# 09_Misc.net
KiCad netlist of a schematic drawn in Altium Designer
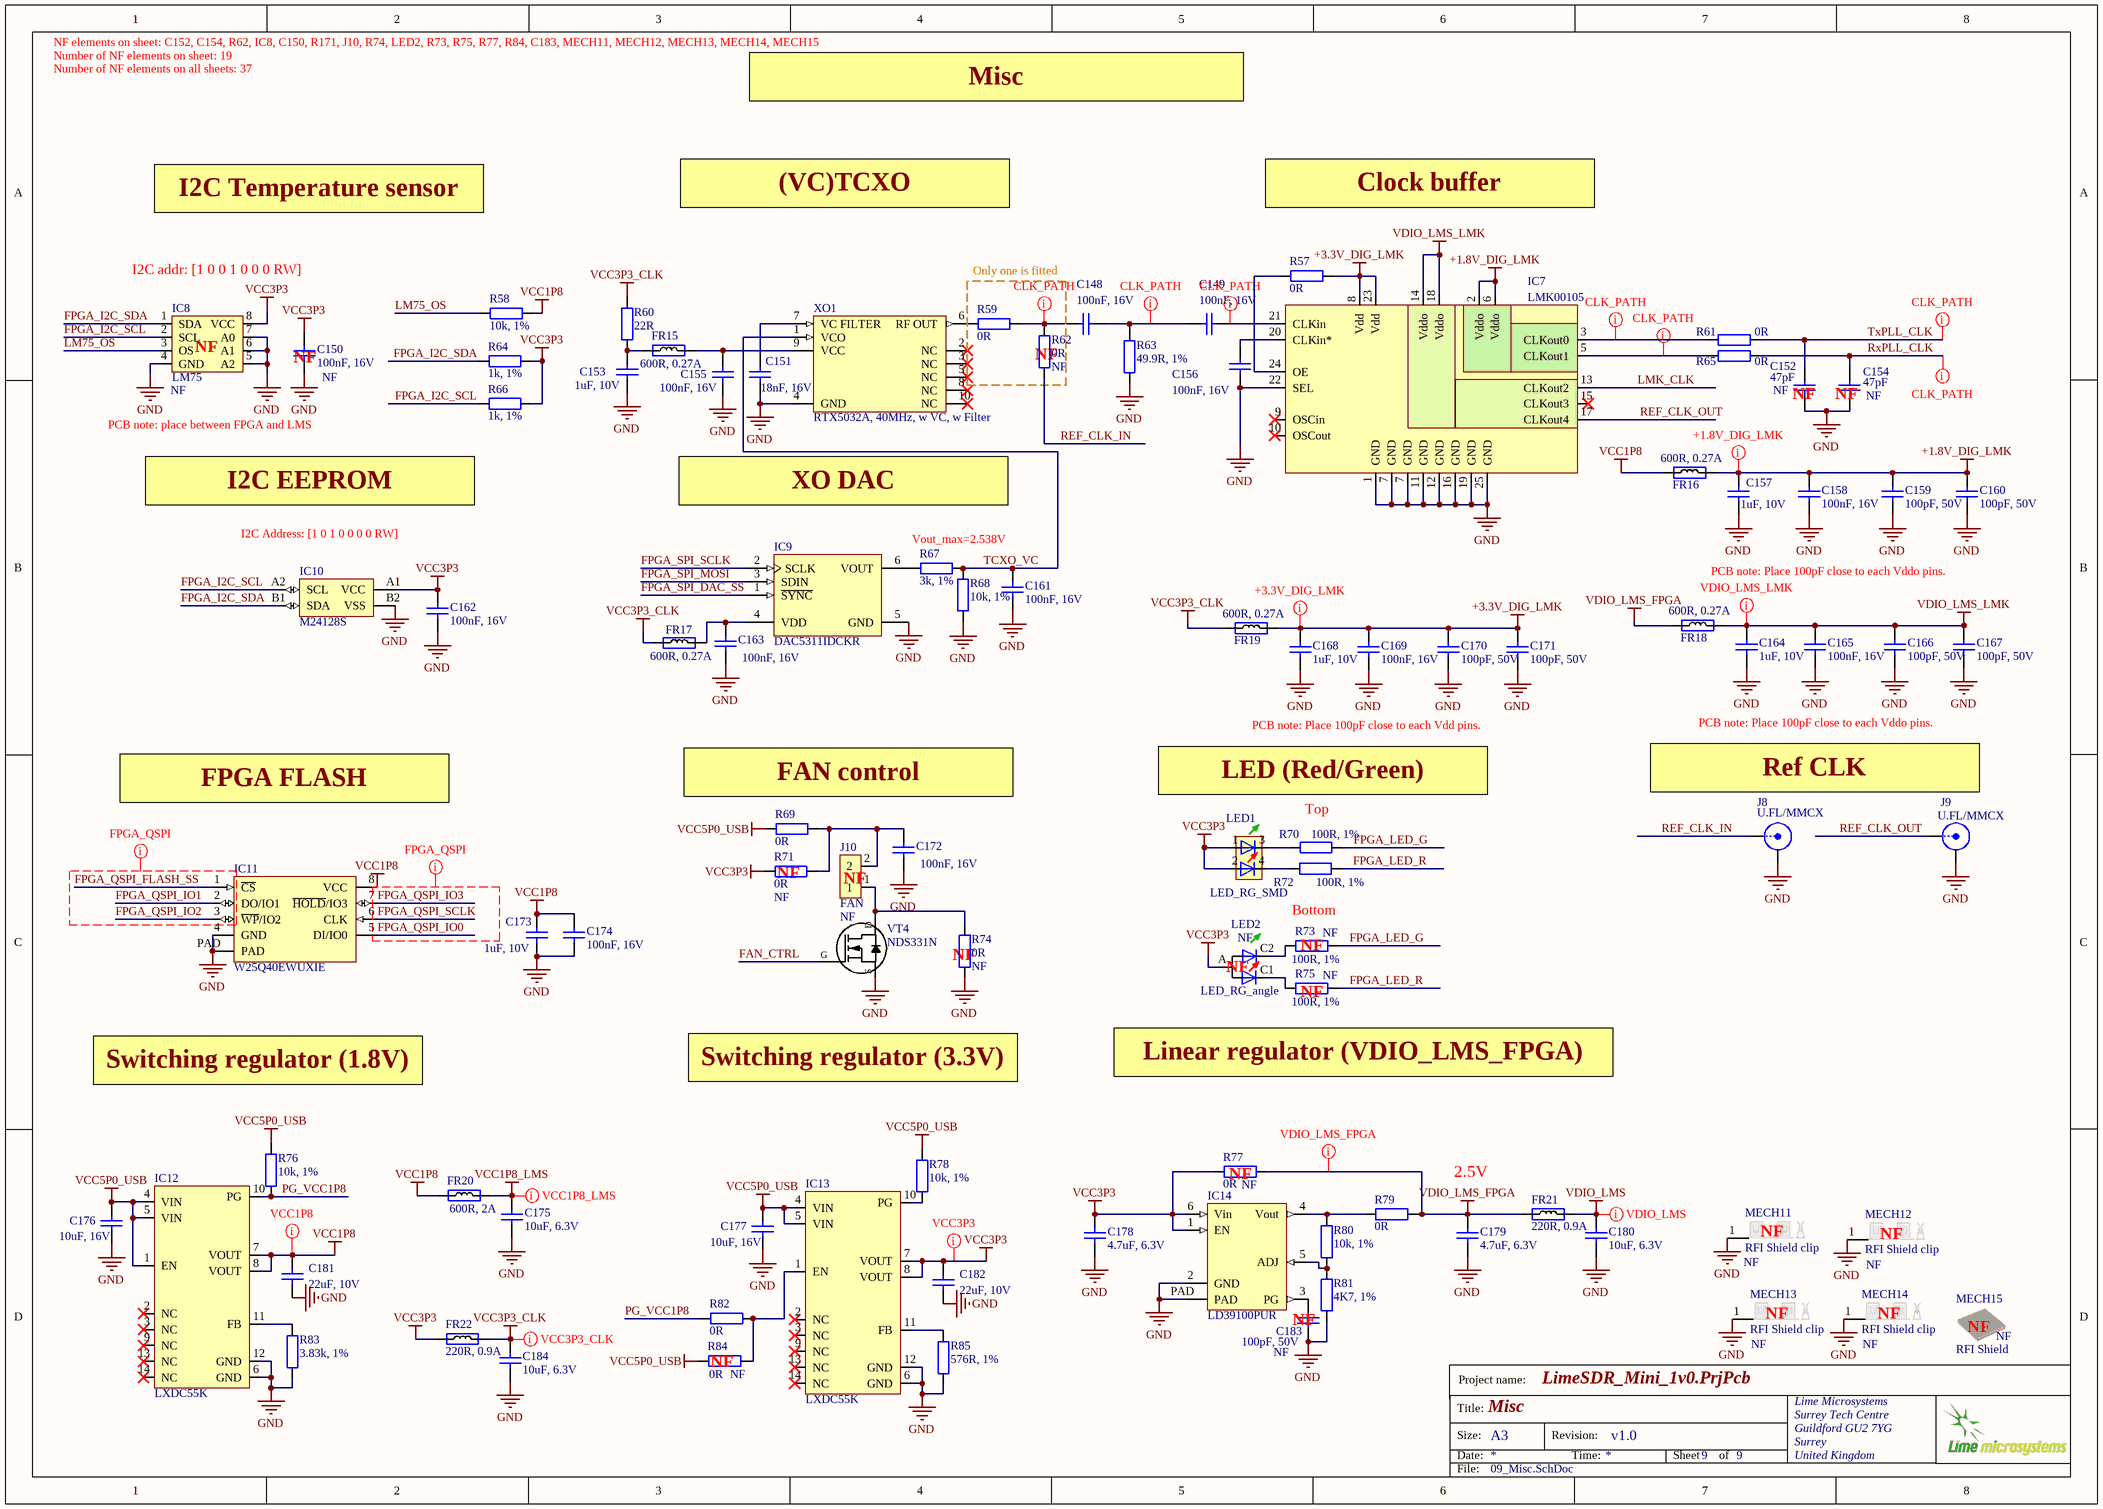
[diagram p0: 09_Misc.SchDoc]

(export (version "E")
  (design (tool "Eeschema 10.0.6"))
  (components
    (comp (ref "C148")
      (value "100nF, 16V")
      (footprint "CAP0402")
      (fields
        (field (name "MANUFACTURER") "Murata Electronics")
        (field (name "TOLERANCE") "10 %")
        (field (name "MANUFACTURER PART NUMBER") "GRM155R71C104KA88D")
      )
      (libsource (lib "LimeMicroAltiumLib_schLib") (part "Cap_0402"))
    )
    (comp (ref "C149")
      (value "100nF, 16V")
      (footprint "CAP0402")
      (fields
        (field (name "MANUFACTURER") "Murata Electronics")
        (field (name "TOLERANCE") "10 %")
        (field (name "MANUFACTURER PART NUMBER") "GRM155R71C104KA88D")
      )
      (libsource (lib "LimeMicroAltiumLib_schLib") (part "Cap_0402"))
    )
    (comp (ref "C150")
      (value "100nF, 16V")
      (footprint "CAP0402")
      (fields
        (field (name "TOLERANCE") "10 %")
        (field (name "MANUFACTURER") "Murata Electronics")
        (field (name "MANUFACTURER PART NUMBER") "GRM155R71C104KA88D")
        (field (name "ASSEMBLY INFO") "NF")
      )
      (libsource (lib "LimeFPGAboard_schLib") (part "Cap_0603"))
    )
    (comp (ref "C151")
      (value "18nF, 16V")
      (footprint "CAP0402")
      (fields (field (name "MANUFACTURER") "Yageo") (field (name "TOLERANCE") "±10%"))
      (libsource (lib "LimeMicroAltiumLib_schLib") (part "Cap_0402"))
    )
    (comp (ref "C152")
      (value "47pF")
      (footprint "CAP0402")
      (fields
        (field (name "TOLERANCE") "±1%")
        (field (name "MANUFACTURER") "TDK Corporation")
        (field (name "ASSEMBLY INFO") "NF")
      )
      (libsource (lib "LimeMicroAltiumLib_schLib") (part "Cap_0402"))
    )
    (comp (ref "C153")
      (value "1uF, 10V")
      (footprint "CAP0402")
      (fields (field (name "MANUFACTURER") "TDK"))
      (libsource (lib "LimeMicroAltiumLib_schLib") (part "Cap_0402"))
    )
    (comp (ref "C154")
      (value "47pF")
      (footprint "CAP0402")
      (fields
        (field (name "TOLERANCE") "±1%")
        (field (name "MANUFACTURER") "TDK Corporation")
        (field (name "ASSEMBLY INFO") "NF")
      )
      (libsource (lib "LimeMicroAltiumLib_schLib") (part "Cap_0402"))
    )
    (comp (ref "C155")
      (value "100nF, 16V")
      (footprint "CAP0402")
      (fields
        (field (name "MANUFACTURER") "Murata Electronics")
        (field (name "TOLERANCE") "10 %")
        (field (name "MANUFACTURER PART NUMBER") "GRM155R71C104KA88D")
      )
      (libsource (lib "LimeMicroAltiumLib_schLib") (part "Cap_0402"))
    )
    (comp (ref "C156")
      (value "100nF, 16V")
      (footprint "CAP0402")
      (fields
        (field (name "MANUFACTURER") "Murata Electronics")
        (field (name "TOLERANCE") "10 %")
        (field (name "MANUFACTURER PART NUMBER") "GRM155R71C104KA88D")
      )
      (libsource (lib "LimeMicroAltiumLib_schLib") (part "Cap_0402"))
    )
    (comp (ref "C157")
      (value "1uF, 10V")
      (footprint "CAP0402")
      (fields (field (name "MANUFACTURER") "TDK"))
      (libsource (lib "LimeMicroAltiumLib_schLib") (part "Cap_0402"))
    )
    (comp (ref "C158")
      (value "100nF, 16V")
      (footprint "CAP0402")
      (fields
        (field (name "MANUFACTURER") "Murata Electronics")
        (field (name "TOLERANCE") "10 %")
        (field (name "MANUFACTURER PART NUMBER") "GRM155R71C104KA88D")
      )
      (libsource (lib "LimeMicroAltiumLib_schLib") (part "Cap_0402"))
    )
    (comp (ref "C159")
      (value "100pF, 50V")
      (footprint "CAP0402")
      (fields (field (name "MANUFACTURER") "Yageo") (field (name "TOLERANCE") "±5%"))
      (libsource (lib "LimeMicroAltiumLib_schLib") (part "Cap_0402"))
    )
    (comp (ref "C160")
      (value "100pF, 50V")
      (footprint "CAP0402")
      (fields (field (name "MANUFACTURER") "Yageo") (field (name "TOLERANCE") "±5%"))
      (libsource (lib "LimeMicroAltiumLib_schLib") (part "Cap_0402"))
    )
    (comp (ref "C161")
      (value "100nF, 16V")
      (footprint "CAP0402")
      (fields
        (field (name "MANUFACTURER") "Murata Electronics")
        (field (name "TOLERANCE") "10 %")
        (field (name "MANUFACTURER PART NUMBER") "GRM155R71C104KA88D")
      )
      (libsource (lib "LimeMicroAltiumLib_schLib") (part "Cap_0402"))
    )
    (comp (ref "C162")
      (value "100nF, 16V")
      (footprint "CAP0402")
      (fields
        (field (name "TOLERANCE") "10 %")
        (field (name "MANUFACTURER") "Murata Electronics")
        (field (name "MANUFACTURER PART NUMBER") "GRM155R71C104KA88D")
      )
      (libsource (lib "LimeFPGAboard_schLib") (part "Cap_0603"))
    )
    (comp (ref "C163")
      (value "100nF, 16V")
      (footprint "CAP0402")
      (fields
        (field (name "TOLERANCE") "10 %")
        (field (name "MANUFACTURER") "Murata Electronics")
        (field (name "MANUFACTURER PART NUMBER") "GRM155R71C104KA88D")
      )
      (libsource (lib "LimeFPGAboard_schLib") (part "Cap_0603"))
    )
    (comp (ref "C164")
      (value "1uF, 10V")
      (footprint "CAP0402")
      (fields (field (name "MANUFACTURER") "TDK"))
      (libsource (lib "LimeMicroAltiumLib_schLib") (part "Cap_0402"))
    )
    (comp (ref "C165")
      (value "100nF, 16V")
      (footprint "CAP0402")
      (fields
        (field (name "MANUFACTURER") "Murata Electronics")
        (field (name "TOLERANCE") "10 %")
        (field (name "MANUFACTURER PART NUMBER") "GRM155R71C104KA88D")
      )
      (libsource (lib "LimeMicroAltiumLib_schLib") (part "Cap_0402"))
    )
    (comp (ref "C166")
      (value "100pF, 50V")
      (footprint "CAP0402")
      (fields (field (name "MANUFACTURER") "Yageo") (field (name "TOLERANCE") "±5%"))
      (libsource (lib "LimeMicroAltiumLib_schLib") (part "Cap_0402"))
    )
    (comp (ref "C167")
      (value "100pF, 50V")
      (footprint "CAP0402")
      (fields (field (name "MANUFACTURER") "Yageo") (field (name "TOLERANCE") "±5%"))
      (libsource (lib "LimeMicroAltiumLib_schLib") (part "Cap_0402"))
    )
    (comp (ref "C168")
      (value "1uF, 10V")
      (footprint "CAP0402")
      (fields (field (name "MANUFACTURER") "TDK"))
      (libsource (lib "LimeMicroAltiumLib_schLib") (part "Cap_0402"))
    )
    (comp (ref "C169")
      (value "100nF, 16V")
      (footprint "CAP0402")
      (fields
        (field (name "MANUFACTURER") "Murata Electronics")
        (field (name "TOLERANCE") "10 %")
        (field (name "MANUFACTURER PART NUMBER") "GRM155R71C104KA88D")
      )
      (libsource (lib "LimeMicroAltiumLib_schLib") (part "Cap_0402"))
    )
    (comp (ref "C170")
      (value "100pF, 50V")
      (footprint "CAP0402")
      (fields (field (name "MANUFACTURER") "Yageo") (field (name "TOLERANCE") "±5%"))
      (libsource (lib "LimeMicroAltiumLib_schLib") (part "Cap_0402"))
    )
    (comp (ref "C171")
      (value "100pF, 50V")
      (footprint "CAP0402")
      (fields (field (name "MANUFACTURER") "Yageo") (field (name "TOLERANCE") "±5%"))
      (libsource (lib "LimeMicroAltiumLib_schLib") (part "Cap_0402"))
    )
    (comp (ref "C172")
      (value "100nF, 16V")
      (footprint "CAP0402")
      (fields
        (field (name "TOLERANCE") "10 %")
        (field (name "MANUFACTURER") "Murata Electronics")
        (field (name "MANUFACTURER PART NUMBER") "GRM155R71C104KA88D")
      )
      (libsource (lib "LimeFPGAboard_schLib") (part "Cap_0603"))
    )
    (comp (ref "C173")
      (value "1uF, 10V")
      (footprint "CAP0402")
      (fields (field (name "MANUFACTURER") "TDK"))
      (libsource (lib "LimeMicroAltiumLib_schLib") (part "Cap_0402"))
    )
    (comp (ref "C174")
      (value "100nF, 16V")
      (footprint "CAP0402")
      (fields
        (field (name "TOLERANCE") "10 %")
        (field (name "MANUFACTURER") "Murata Electronics")
        (field (name "MANUFACTURER PART NUMBER") "GRM155R71C104KA88D")
      )
      (libsource (lib "LimeFPGAboard_schLib") (part "Cap_0603"))
    )
    (comp (ref "C175")
      (value "10uF, 6.3V")
      (footprint "CAP0603")
      (fields (field (name "TOLERANCE") "±20%") (field (name "MANUFACTURER") "Yageo"))
      (libsource (lib "LimeFPGAboard_schLib") (part "Cap_0603"))
    )
    (comp (ref "C176")
      (value "10uF, 16V")
      (footprint "CAP0603")
      (fields (field (name "MANUFACTURER") "Yageo") (field (name "TOLERANCE") "±20%"))
      (libsource (lib "LimeMicroAltiumLib_schLib") (part "Cap_0603"))
    )
    (comp (ref "C177")
      (value "10uF, 16V")
      (footprint "CAP0603")
      (fields (field (name "MANUFACTURER") "Yageo") (field (name "TOLERANCE") "±20%"))
      (libsource (lib "LimeMicroAltiumLib_schLib") (part "Cap_0603"))
    )
    (comp (ref "C178")
      (value "4.7uF, 6.3V")
      (footprint "CAP0402")
      (fields
        (field (name "MANUFACTURER") "Murata Electronics North America")
        (field (name "TOLERANCE") "±20%")
        (field (name "MANUFACTURER PART NUMBER") "GRM155R60J475ME87D")
      )
      (libsource (lib "LimeMicroAltiumLib_schLib") (part "Cap_0402"))
    )
    (comp (ref "C179")
      (value "4.7uF, 6.3V")
      (footprint "CAP0402")
      (fields
        (field (name "MANUFACTURER") "Murata Electronics North America")
        (field (name "TOLERANCE") "±20%")
        (field (name "MANUFACTURER PART NUMBER") "GRM155R60J475ME87D")
      )
      (libsource (lib "LimeMicroAltiumLib_schLib") (part "Cap_0402"))
    )
    (comp (ref "C180")
      (value "10uF, 6.3V")
      (footprint "CAP0603")
      (fields (field (name "TOLERANCE") "±20%") (field (name "MANUFACTURER") "Yageo"))
      (libsource (lib "LimeFPGAboard_schLib") (part "Cap_0603"))
    )
    (comp (ref "C181")
      (value "22uF, 10V")
      (footprint "CAP0603")
      (fields (field (name "TOLERANCE") "20 %") (field (name "MANUFACTURER") "TDK Corporation"))
      (libsource (lib "LimeFPGAboard_schLib") (part "Cap_0603"))
    )
    (comp (ref "C182")
      (value "22uF, 10V")
      (footprint "CAP0603")
      (fields (field (name "TOLERANCE") "20 %") (field (name "MANUFACTURER") "TDK Corporation"))
      (libsource (lib "LimeFPGAboard_schLib") (part "Cap_0603"))
    )
    (comp (ref "C183")
      (value "100pF, 50V")
      (footprint "CAP0402")
      (fields
        (field (name "ASSEMBLY INFO") "NF")
        (field (name "MANUFACTURER") "Yageo")
        (field (name "TOLERANCE") "±5%")
      )
      (libsource (lib "LimeMicroAltiumLib_schLib") (part "Cap_0402"))
    )
    (comp (ref "C184")
      (value "10uF, 6.3V")
      (footprint "CAP0603")
      (fields (field (name "TOLERANCE") "±20%") (field (name "MANUFACTURER") "Yageo"))
      (libsource (lib "LimeFPGAboard_schLib") (part "Cap_0603"))
    )
    (comp (ref "FR15")
      (value "600R, 0.27A")
      (footprint "RES0201")
      (fields (field (name "MANUFACTURER") "Taiyo Yuden"))
      (libsource (lib "LimeMicroAltiumLib_schLib") (part "Ferrite"))
    )
    (comp (ref "FR16")
      (value "600R, 0.27A")
      (footprint "RES0201")
      (fields (field (name "MANUFACTURER") "Taiyo Yuden"))
      (libsource (lib "LimeMicroAltiumLib_schLib") (part "Ferrite"))
    )
    (comp (ref "FR17")
      (value "600R, 0.27A")
      (footprint "RES0201")
      (fields (field (name "MANUFACTURER") "Taiyo Yuden"))
      (libsource (lib "LimeMicroAltiumLib_schLib") (part "Ferrite"))
    )
    (comp (ref "FR18")
      (value "600R, 0.27A")
      (footprint "RES0201")
      (fields (field (name "MANUFACTURER") "Taiyo Yuden"))
      (libsource (lib "LimeMicroAltiumLib_schLib") (part "Ferrite"))
    )
    (comp (ref "FR19")
      (value "600R, 0.27A")
      (footprint "RES0201")
      (fields (field (name "MANUFACTURER") "Taiyo Yuden"))
      (libsource (lib "LimeMicroAltiumLib_schLib") (part "Ferrite"))
    )
    (comp (ref "FR20")
      (value "600R, 2A")
      (footprint "RES0805")
      (fields (field (name "MANUFACTURER") "TDK Corporation"))
      (libsource (lib "LimeMicroAltiumLib_schLib") (part "Ferrite"))
    )
    (comp (ref "FR21")
      (value "220R, 0.9A")
      (footprint "RES0402")
      (fields (field (name "MANUFACTURER") "TDK Corporation"))
      (libsource (lib "LimeFPGAboard_schLib") (part "Ferrite"))
    )
    (comp (ref "FR22")
      (value "220R, 0.9A")
      (footprint "RES0402")
      (fields (field (name "MANUFACTURER") "TDK Corporation"))
      (libsource (lib "LimeFPGAboard_schLib") (part "Ferrite"))
    )
    (comp (ref "IC7")
      (value "LMK00105")
      (footprint "LMK00105SQ")
      (fields (field (name "MANUFACTURER") "Texas Instruments"))
      (libsource (lib "LimeMicroAltiumLib_schLib") (part "LMK00105"))
    )
    (comp (ref "IC8")
      (value "LM75")
      (footprint "HWSON8_LM75")
      (fields
        (field (name "MANUFACTURER") "NXP Semiconductors")
        (field (name "MANUFACTURER PART NUMBER") "LM75BTP,147")
        (field (name "ASSEMBLY INFO") "NF")
      )
      (libsource (lib "LimeMicroAltiumLib_schLib") (part "LM75"))
    )
    (comp (ref "IC9")
      (value "DAC5311IDCKR")
      (footprint "AD5601_SOT23-6")
      (fields (field (name "MANUFACTURER") "Texas Instruments"))
      (libsource (lib "LimeMicroAltiumLib_schLib") (part "AD5601BKSZ-REEL7"))
    )
    (comp (ref "IC10")
      (value "M24128S")
      (footprint "M24128S")
      (fields (field (name "MANUFACTURER") "STMicroelectronics"))
      (libsource (lib "LimeMicroAltiumLib_schLib") (part "M24128S"))
    )
    (comp (ref "IC11")
      (value "W25Q40EWUXIE")
      (footprint "W25Q40EWUXIE_8-USON")
      (fields (field (name "MANUFACTURER") "Winbond Electronics"))
      (libsource (lib "LimeMicroAltiumLib_schLib") (part "W25Q40EWUXIE"))
    )
    (comp (ref "IC12")
      (value "LXDC55K")
      (footprint "LXDC55K")
      (description "LXDC55KAAA-205")
      (fields (field (name "MANUFACTURER") "Murata Electronics North America"))
      (libsource (lib "LimeMicroAltiumLib_schLib") (part "LXDC55K"))
    )
    (comp (ref "IC13")
      (value "LXDC55K")
      (footprint "LXDC55K")
      (description "LXDC55KAAA-205")
      (fields (field (name "MANUFACTURER") "Murata Electronics North America"))
      (libsource (lib "LimeMicroAltiumLib_schLib") (part "LXDC55K"))
    )
    (comp (ref "IC14")
      (value "LD39100PUR")
      (footprint "LD39100PUR")
      (fields (field (name "MANUFACTURER") "STMicroelectronics"))
      (libsource (lib "LimeMicroAltiumLib_schLib") (part "LD39100PUR"))
    )
    (comp (ref "J8")
      (value "U.FL/MMCX")
      (footprint "MMCX_UFL_conn_u")
      (description "CONN UMC RCPT STR 50 OHM SMD")
      (fields (field (name "MANUFACTURER") "Molex, LLC"))
      (libsource (lib "LimeMicroAltiumLib_schLib") (part "RF_IF_connector"))
    )
    (comp (ref "J9")
      (value "U.FL/MMCX")
      (footprint "MMCX_UFL_conn_u")
      (description "CONN UMC RCPT STR 50 OHM SMD")
      (fields (field (name "MANUFACTURER") "Molex, LLC"))
      (libsource (lib "LimeMicroAltiumLib_schLib") (part "RF_IF_connector"))
    )
    (comp (ref "J10")
      (value "FAN")
      (footprint "HDR_1x2_v2")
      (fields (field (name "ASSEMBLY INFO") "NF") (field (name "MANUFACTURER") "3M"))
      (libsource (lib "LimeFPGAboard_schLib") (part "Jumper"))
    )
    (comp (ref "LED1")
      (value "LED_RG_SMD")
      (footprint "LED-2x0603")
      (fields (field (name "MANUFACTURER") "Avago Technologies US Inc."))
      (libsource (lib "LimeMicroAltiumLib_schLib") (part "LED_green_red_SMD"))
    )
    (comp (ref "LED2")
      (value "LED_RG_angle")
      (footprint "LED_RG_RIGHT_ANGLE_v2")
      (description "160-2033-1-ND")
      (fields (field (name "MANUFACTURER") "Lite-On") (field (name "ASSEMBLY INFO") "NF"))
      (libsource (lib "LimeMicroAltiumLib_schLib") (part "LED_green_red_right_angle"))
    )
    (comp (ref "MECH11")
      (value "RFI Shield clip")
      (footprint "RFI_SHIELD_CLPS_MINI")
      (fields (field (name "MANUFACTURER") "HARWIN") (field (name "ASSEMBLY INFO") "NF"))
      (libsource (lib "LimeMicroAltiumLib_schLib") (part "RFI_SHIELD_CLIP"))
    )
    (comp (ref "MECH12")
      (value "RFI Shield clip")
      (footprint "RFI_SHIELD_CLPS_MINI")
      (fields (field (name "MANUFACTURER") "HARWIN") (field (name "ASSEMBLY INFO") "NF"))
      (libsource (lib "LimeMicroAltiumLib_schLib") (part "RFI_SHIELD_CLIP"))
    )
    (comp (ref "MECH13")
      (value "RFI Shield clip")
      (footprint "RFI_SHIELD_CLPS_MINI")
      (fields (field (name "MANUFACTURER") "HARWIN") (field (name "ASSEMBLY INFO") "NF"))
      (libsource (lib "LimeMicroAltiumLib_schLib") (part "RFI_SHIELD_CLIP"))
    )
    (comp (ref "MECH14")
      (value "RFI Shield clip")
      (footprint "RFI_SHIELD_CLPS_MINI")
      (fields (field (name "MANUFACTURER") "HARWIN") (field (name "ASSEMBLY INFO") "NF"))
      (libsource (lib "LimeMicroAltiumLib_schLib") (part "RFI_SHIELD_CLIP"))
    )
    (comp (ref "MECH15")
      (value "RFI Shield")
      (footprint "WurthElectronic_RF_shield")
      (fields (field (name "MANUFACTURER") "WURTH ELEKTRONIK") (field (name "ASSEMBLY INFO") "NF"))
      (libsource (lib "LimeMicroAltiumLib_schLib") (part "RFI_SHIELD_1"))
    )
    (comp (ref "R57")
      (value "0R")
      (footprint "RES0402")
      (fields (field (name "MANUFACTURER") "Yageo") (field (name "TOLERANCE") "Jumper"))
      (libsource (lib "LimeMicroAltiumLib_schLib") (part "Res_0402"))
    )
    (comp (ref "R58")
      (value "10k, 1%")
      (footprint "RES0402")
      (fields (field (name "MANUFACTURER") "Yageo") (field (name "TOLERANCE") "±1%"))
      (libsource (lib "LimeMicroAltiumLib_schLib") (part "Res_0402"))
    )
    (comp (ref "R59")
      (value "0R")
      (footprint "RES0402")
      (fields (field (name "MANUFACTURER") "Yageo") (field (name "TOLERANCE") "Jumper"))
      (libsource (lib "LimeMicroAltiumLib_schLib") (part "Res_0402"))
    )
    (comp (ref "R60")
      (value "22R")
      (footprint "RES0402")
      (fields (field (name "TOLERANCE") "±1%") (field (name "MANUFACTURER") "Yageo"))
      (libsource (lib "LimeFPGAboard_schLib") (part "Res_0402"))
    )
    (comp (ref "R61")
      (value "0R")
      (footprint "RES0402")
      (fields (field (name "MANUFACTURER") "Yageo"))
      (libsource (lib "LimeFPGAboard_schLib") (part "Res_0402"))
    )
    (comp (ref "R62")
      (value "0R")
      (footprint "RES0402")
      (fields
        (field (name "ASSEMBLY INFO") "NF")
        (field (name "MANUFACTURER") "Yageo")
        (field (name "TOLERANCE") "Jumper")
      )
      (libsource (lib "LimeMicroAltiumLib_schLib") (part "Res_0402"))
    )
    (comp (ref "R63")
      (value "49.9R, 1%")
      (footprint "RES0402")
      (fields
        (field (name "TOLERANCE") "±1%")
        (field (name "MANUFACTURER") "Samsung Electro-Mechanics America, Inc.")
        (field (name "MANUFACTURER PART NUMBER") "RC1005F49R9CS")
      )
      (libsource (lib "LimeMicroAltiumLib_schLib") (part "Res_0402"))
    )
    (comp (ref "R64")
      (value "1k, 1%")
      (footprint "RES0402")
      (fields (field (name "MANUFACTURER") "Stackpole Electronics Inc") (field (name "TOLERANCE") "±1%"))
      (libsource (lib "LimeMicroAltiumLib_schLib") (part "Res_0402"))
    )
    (comp (ref "R65")
      (value "0R")
      (footprint "RES0402")
      (fields (field (name "MANUFACTURER") "Yageo"))
      (libsource (lib "LimeFPGAboard_schLib") (part "Res_0402"))
    )
    (comp (ref "R66")
      (value "1k, 1%")
      (footprint "RES0402")
      (fields (field (name "MANUFACTURER") "Stackpole Electronics Inc") (field (name "TOLERANCE") "±1%"))
      (libsource (lib "LimeMicroAltiumLib_schLib") (part "Res_0402"))
    )
    (comp (ref "R67")
      (value "3k, 1%")
      (footprint "RES0402")
      (fields (field (name "TOLERANCE") "±1%") (field (name "MANUFACTURER") "Vishay Dale"))
      (libsource (lib "LimeMicroAltiumLib_schLib") (part "Res_0402"))
    )
    (comp (ref "R68")
      (value "10k, 1%")
      (footprint "RES0402")
      (fields (field (name "MANUFACTURER") "Yageo") (field (name "TOLERANCE") "±1%"))
      (libsource (lib "LimeMicroAltiumLib_schLib") (part "Res_0402"))
    )
    (comp (ref "R69")
      (value "0R")
      (footprint "RES0402")
      (fields (field (name "MANUFACTURER") "Yageo") (field (name "TOLERANCE") "Jumper"))
      (libsource (lib "LimeMicroAltiumLib_schLib") (part "Res_0402"))
    )
    (comp (ref "R70")
      (value "100R, 1%")
      (footprint "RES0402")
      (fields (field (name "TOLERANCE") "±1%") (field (name "MANUFACTURER") "Stackpole Electronics Inc."))
      (libsource (lib "LimeMicroAltiumLib_schLib") (part "Res_0402"))
    )
    (comp (ref "R71")
      (value "0R")
      (footprint "RES0402")
      (fields
        (field (name "ASSEMBLY INFO") "NF")
        (field (name "MANUFACTURER") "Yageo")
        (field (name "TOLERANCE") "Jumper")
      )
      (libsource (lib "LimeMicroAltiumLib_schLib") (part "Res_0402"))
    )
    (comp (ref "R72")
      (value "100R, 1%")
      (footprint "RES0402")
      (fields (field (name "TOLERANCE") "±1%") (field (name "MANUFACTURER") "Stackpole Electronics Inc."))
      (libsource (lib "LimeMicroAltiumLib_schLib") (part "Res_0402"))
    )
    (comp (ref "R73")
      (value "100R, 1%")
      (footprint "RES0402")
      (fields
        (field (name "TOLERANCE") "±1%")
        (field (name "MANUFACTURER") "Stackpole Electronics Inc.")
        (field (name "ASSEMBLY INFO") "NF")
      )
      (libsource (lib "LimeMicroAltiumLib_schLib") (part "Res_0402"))
    )
    (comp (ref "R74")
      (value "0R")
      (footprint "RES0402")
      (fields
        (field (name "ASSEMBLY INFO") "NF")
        (field (name "MANUFACTURER") "Yageo")
        (field (name "TOLERANCE") "Jumper")
      )
      (libsource (lib "LimeMicroAltiumLib_schLib") (part "Res_0402"))
    )
    (comp (ref "R75")
      (value "100R, 1%")
      (footprint "RES0402")
      (fields
        (field (name "TOLERANCE") "±1%")
        (field (name "MANUFACTURER") "Stackpole Electronics Inc.")
        (field (name "ASSEMBLY INFO") "NF")
      )
      (libsource (lib "LimeMicroAltiumLib_schLib") (part "Res_0402"))
    )
    (comp (ref "R76")
      (value "10k, 1%")
      (footprint "RES0402")
      (fields (field (name "MANUFACTURER") "Yageo") (field (name "TOLERANCE") "±1%"))
      (libsource (lib "LimeMicroAltiumLib_schLib") (part "Res_0402"))
    )
    (comp (ref "R77")
      (value "0R")
      (footprint "RES0402")
      (fields (field (name "MANUFACTURER") "Yageo") (field (name "ASSEMBLY INFO") "NF"))
      (libsource (lib "LimeFPGAboard_schLib") (part "Res_0402"))
    )
    (comp (ref "R78")
      (value "10k, 1%")
      (footprint "RES0402")
      (fields (field (name "MANUFACTURER") "Yageo") (field (name "TOLERANCE") "±1%"))
      (libsource (lib "LimeMicroAltiumLib_schLib") (part "Res_0402"))
    )
    (comp (ref "R79")
      (value "0R")
      (footprint "RES0402")
      (fields (field (name "MANUFACTURER") "Yageo"))
      (libsource (lib "LimeFPGAboard_schLib") (part "Res_0402"))
    )
    (comp (ref "R80")
      (value "10k, 1%")
      (footprint "RES0402")
      (fields (field (name "MANUFACTURER") "Yageo") (field (name "TOLERANCE") "±1%"))
      (libsource (lib "LimeMicroAltiumLib_schLib") (part "Res_0402"))
    )
    (comp (ref "R81")
      (value "4K7, 1%")
      (footprint "RES0402")
      (fields (field (name "MANUFACTURER") "Yageo") (field (name "TOLERANCE") "±1%"))
      (libsource (lib "LimeFPGAboard_schLib") (part "Res_0402"))
    )
    (comp (ref "R82")
      (value "0R")
      (footprint "RES0402")
      (fields (field (name "MANUFACTURER") "Yageo") (field (name "TOLERANCE") "Jumper"))
      (libsource (lib "LimeMicroAltiumLib_schLib") (part "Res_0402"))
    )
    (comp (ref "R83")
      (value "3.83k, 1%")
      (footprint "RES0402")
      (fields (field (name "TOLERANCE") "±1%") (field (name "MANUFACTURER") "Stackpole Electronics Inc."))
      (libsource (lib "LimeMicroAltiumLib_schLib") (part "Res_0402"))
    )
    (comp (ref "R84")
      (value "0R")
      (footprint "RES0402")
      (fields
        (field (name "ASSEMBLY INFO") "NF")
        (field (name "MANUFACTURER") "Yageo")
        (field (name "TOLERANCE") "Jumper")
      )
      (libsource (lib "LimeMicroAltiumLib_schLib") (part "Res_0402"))
    )
    (comp (ref "R85")
      (value "576R, 1%")
      (footprint "RES0402")
      (fields (field (name "TOLERANCE") "±1%") (field (name "MANUFACTURER") "Yageo"))
      (libsource (lib "LimeMicroAltiumLib_schLib") (part "Res_0402"))
    )
    (comp (ref "VT4")
      (value "NDS331N")
      (footprint "SOT23-3")
      (fields (field (name "MANUFACTURER") "FAIRCHILD SEMICONDUCTOR"))
      (libsource (lib "LimeFPGAboard_schLib") (part "NDS331N"))
    )
    (comp (ref "XO1")
      (value "RTX5032A, 40MHz, w VC, w Filter")
      (footprint "RAKON_RTX5032A")
      (fields (field (name "MANUFACTURER") "Rakon"))
      (libsource (lib "LimeMicroAltiumLib_schLib") (part "Rakon_RTX5032A"))
    )
  )
  (nets
    (net (code "1") (name "+1.8V_DIG_LMK") (class "Default")
      (node (ref "C157") (pin "2") (pinfunction "2_2") (pintype "passive"))
      (node (ref "C158") (pin "2") (pinfunction "2_2") (pintype "passive"))
      (node (ref "C159") (pin "2") (pinfunction "2_2") (pintype "passive"))
      (node (ref "C160") (pin "2") (pinfunction "2_2") (pintype "passive"))
      (node (ref "FR16") (pin "2") (pinfunction "2_2") (pintype "passive"))
      (node (ref "IC7") (pin "2") (pinfunction "Vddo_2") (pintype "passive"))
      (node (ref "IC7") (pin "6") (pinfunction "Vddo_6") (pintype "passive"))
    )
    (net (code "2") (name "+3.3V_DIG_LMK") (class "Default")
      (node (ref "C168") (pin "2") (pinfunction "2_2") (pintype "passive"))
      (node (ref "C169") (pin "2") (pinfunction "2_2") (pintype "passive"))
      (node (ref "C170") (pin "2") (pinfunction "2_2") (pintype "passive"))
      (node (ref "C171") (pin "2") (pinfunction "2_2") (pintype "passive"))
      (node (ref "FR19") (pin "2") (pinfunction "2_2") (pintype "passive"))
      (node (ref "IC7") (pin "23") (pinfunction "Vdd_23") (pintype "passive"))
      (node (ref "IC7") (pin "8") (pinfunction "Vdd_8") (pintype "passive"))
      (node (ref "R57") (pin "2") (pinfunction "2_2") (pintype "passive"))
    )
    (net (code "3") (name "/FAN_CTRL") (class "Default")
      (node (ref "VT4") (pin "G") (pinfunction "G_G") (pintype "passive"))
    )
    (net (code "4") (name "/FPGA_I2C_SCL") (class "Default")
      (node (ref "IC10") (pin "A2") (pinfunction "SCL_A2") (pintype "bidirectional"))
      (node (ref "IC8") (pin "2") (pinfunction "SCL_2") (pintype "passive"))
      (node (ref "R66") (pin "2") (pinfunction "2_2") (pintype "passive"))
    )
    (net (code "5") (name "/FPGA_I2C_SDA") (class "Default")
      (node (ref "IC10") (pin "B1") (pinfunction "SDA_B1") (pintype "bidirectional"))
      (node (ref "IC8") (pin "1") (pinfunction "SDA_1") (pintype "passive"))
      (node (ref "R64") (pin "2") (pinfunction "2_2") (pintype "passive"))
    )
    (net (code "6") (name "/FPGA_LED_G") (class "Default")
      (node (ref "R70") (pin "2") (pinfunction "2_2") (pintype "passive"))
      (node (ref "R73") (pin "2") (pinfunction "2_2") (pintype "passive"))
    )
    (net (code "7") (name "/FPGA_LED_R") (class "Default")
      (node (ref "R72") (pin "2") (pinfunction "2_2") (pintype "passive"))
      (node (ref "R75") (pin "2") (pinfunction "2_2") (pintype "passive"))
    )
    (net (code "8") (name "/FPGA_QSPI_FLASH_SS") (class "Default")
      (node (ref "IC11") (pin "1") (pinfunction "~{CS}_1") (pintype "input"))
    )
    (net (code "9") (name "/FPGA_QSPI_IO0") (class "Default")
      (node (ref "IC11") (pin "5") (pinfunction "DI/IO0_5") (pintype "passive"))
    )
    (net (code "10") (name "/FPGA_QSPI_IO1") (class "Default")
      (node (ref "IC11") (pin "2") (pinfunction "DO/IO1_2") (pintype "bidirectional"))
    )
    (net (code "11") (name "/FPGA_QSPI_IO2") (class "Default")
      (node (ref "IC11") (pin "3") (pinfunction "~{WP}/IO2_3") (pintype "bidirectional"))
    )
    (net (code "12") (name "/FPGA_QSPI_IO3") (class "Default")
      (node (ref "IC11") (pin "7") (pinfunction "~{HOLD}/IO3_7") (pintype "bidirectional"))
    )
    (net (code "13") (name "/FPGA_QSPI_SCLK") (class "Default")
      (node (ref "IC11") (pin "6") (pinfunction "CLK_6") (pintype "input"))
    )
    (net (code "14") (name "/FPGA_SPI_DAC_SS") (class "Default")
      (node (ref "IC9") (pin "1") (pinfunction "~{SYNC}_1") (pintype "input"))
    )
    (net (code "15") (name "/FPGA_SPI_MOSI") (class "Default")
      (node (ref "IC9") (pin "3") (pinfunction "SDIN_3") (pintype "input"))
    )
    (net (code "16") (name "/FPGA_SPI_SCLK") (class "Default")
      (node (ref "IC9") (pin "2") (pinfunction "SCLK_2") (pintype "input"))
    )
    (net (code "17") (name "/LM75_OS") (class "Default")
      (node (ref "IC8") (pin "3") (pinfunction "OS_3") (pintype "passive"))
      (node (ref "R58") (pin "1") (pinfunction "1_1") (pintype "passive"))
    )
    (net (code "18") (name "/LMK_CLK") (class "Default")
      (node (ref "IC7") (pin "13") (pinfunction "CLKout2_13") (pintype "passive"))
    )
    (net (code "19") (name "/PG_VCC1P8") (class "Default")
      (node (ref "IC12") (pin "10") (pinfunction "PG_10") (pintype "passive"))
      (node (ref "R76") (pin "1") (pinfunction "1_1") (pintype "passive"))
      (node (ref "R82") (pin "2") (pinfunction "2_2") (pintype "passive"))
    )
    (net (code "20") (name "/REF_CLK_IN") (class "Default")
      (node (ref "J8") (pin "1") (pinfunction "X_1") (pintype "passive"))
      (node (ref "R62") (pin "1") (pinfunction "1_1") (pintype "passive"))
    )
    (net (code "21") (name "/REF_CLK_OUT") (class "Default")
      (node (ref "IC7") (pin "17") (pinfunction "CLKout4_17") (pintype "passive"))
      (node (ref "J9") (pin "1") (pinfunction "X_1") (pintype "passive"))
    )
    (net (code "22") (name "/RxPLL_CLK") (class "Default")
      (node (ref "C154") (pin "2") (pinfunction "2_2") (pintype "passive"))
      (node (ref "R65") (pin "1") (pinfunction "1_1") (pintype "passive"))
    )
    (net (code "23") (name "/TCXO_VC") (class "Default")
      (node (ref "C161") (pin "2") (pinfunction "2_2") (pintype "passive"))
      (node (ref "R67") (pin "1") (pinfunction "1_1") (pintype "passive"))
      (node (ref "R68") (pin "1") (pinfunction "1_1") (pintype "passive"))
      (node (ref "XO1") (pin "1") (pinfunction "VCO_1") (pintype "input"))
    )
    (net (code "24") (name "/TxPLL_CLK") (class "Default")
      (node (ref "C152") (pin "2") (pinfunction "2_2") (pintype "passive"))
      (node (ref "R61") (pin "1") (pinfunction "1_1") (pintype "passive"))
    )
    (net (code "25") (name "GND") (class "Default")
      (node (ref "C150") (pin "2") (pinfunction "2_2") (pintype "passive"))
      (node (ref "C151") (pin "1") (pinfunction "1_1") (pintype "passive"))
      (node (ref "C152") (pin "1") (pinfunction "1_1") (pintype "passive"))
      (node (ref "C153") (pin "1") (pinfunction "1_1") (pintype "passive"))
      (node (ref "C154") (pin "1") (pinfunction "1_1") (pintype "passive"))
      (node (ref "C155") (pin "1") (pinfunction "1_1") (pintype "passive"))
      (node (ref "C156") (pin "1") (pinfunction "1_1") (pintype "passive"))
      (node (ref "C157") (pin "1") (pinfunction "1_1") (pintype "passive"))
      (node (ref "C158") (pin "1") (pinfunction "1_1") (pintype "passive"))
      (node (ref "C159") (pin "1") (pinfunction "1_1") (pintype "passive"))
      (node (ref "C160") (pin "1") (pinfunction "1_1") (pintype "passive"))
      (node (ref "C161") (pin "1") (pinfunction "1_1") (pintype "passive"))
      (node (ref "C162") (pin "2") (pinfunction "2_2") (pintype "passive"))
      (node (ref "C163") (pin "2") (pinfunction "2_2") (pintype "passive"))
      (node (ref "C164") (pin "1") (pinfunction "1_1") (pintype "passive"))
      (node (ref "C165") (pin "1") (pinfunction "1_1") (pintype "passive"))
      (node (ref "C166") (pin "1") (pinfunction "1_1") (pintype "passive"))
      (node (ref "C167") (pin "1") (pinfunction "1_1") (pintype "passive"))
      (node (ref "C168") (pin "1") (pinfunction "1_1") (pintype "passive"))
      (node (ref "C169") (pin "1") (pinfunction "1_1") (pintype "passive"))
      (node (ref "C170") (pin "1") (pinfunction "1_1") (pintype "passive"))
      (node (ref "C171") (pin "1") (pinfunction "1_1") (pintype "passive"))
      (node (ref "C172") (pin "2") (pinfunction "2_2") (pintype "passive"))
      (node (ref "C173") (pin "1") (pinfunction "1_1") (pintype "passive"))
      (node (ref "C174") (pin "2") (pinfunction "2_2") (pintype "passive"))
      (node (ref "C175") (pin "1") (pinfunction "1_1") (pintype "passive"))
      (node (ref "C176") (pin "1") (pinfunction "1_1") (pintype "passive"))
      (node (ref "C177") (pin "1") (pinfunction "1_1") (pintype "passive"))
      (node (ref "C178") (pin "1") (pinfunction "1_1") (pintype "passive"))
      (node (ref "C179") (pin "1") (pinfunction "1_1") (pintype "passive"))
      (node (ref "C180") (pin "1") (pinfunction "1_1") (pintype "passive"))
      (node (ref "C181") (pin "1") (pinfunction "1_1") (pintype "passive"))
      (node (ref "C182") (pin "1") (pinfunction "1_1") (pintype "passive"))
      (node (ref "C183") (pin "1") (pinfunction "1_1") (pintype "passive"))
      (node (ref "C184") (pin "1") (pinfunction "1_1") (pintype "passive"))
      (node (ref "IC10") (pin "B2") (pinfunction "VSS_B2") (pintype "passive"))
      (node (ref "IC11") (pin "4") (pinfunction "GND_4") (pintype "passive"))
      (node (ref "IC11") (pin "PAD") (pinfunction "PAD_PAD") (pintype "passive"))
      (node (ref "IC12") (pin "12") (pinfunction "GND_12") (pintype "passive"))
      (node (ref "IC12") (pin "6") (pinfunction "GND_6") (pintype "passive"))
      (node (ref "IC13") (pin "12") (pinfunction "GND_12") (pintype "passive"))
      (node (ref "IC13") (pin "6") (pinfunction "GND_6") (pintype "passive"))
      (node (ref "IC14") (pin "2") (pinfunction "GND_2") (pintype "passive"))
      (node (ref "IC14") (pin "PAD") (pinfunction "PAD_PAD") (pintype "passive"))
      (node (ref "IC7") (pin "1") (pinfunction "GND_1") (pintype "passive"))
      (node (ref "IC7") (pin "11") (pinfunction "GND_11") (pintype "passive"))
      (node (ref "IC7") (pin "12") (pinfunction "GND_12") (pintype "passive"))
      (node (ref "IC7") (pin "16") (pinfunction "GND_16") (pintype "passive"))
      (node (ref "IC7") (pin "19") (pinfunction "GND_19") (pintype "passive"))
      (node (ref "IC7") (pin "22") (pinfunction "SEL_22") (pintype "passive"))
      (node (ref "IC7") (pin "25") (pinfunction "GND_25") (pintype "passive"))
      (node (ref "IC7") (pin "7") (pinfunction "GND_7") (pintype "passive"))
      (node (ref "IC8") (pin "4") (pinfunction "GND_4") (pintype "passive"))
      (node (ref "IC8") (pin "5") (pinfunction "A2_5") (pintype "passive"))
      (node (ref "IC8") (pin "6") (pinfunction "A1_6") (pintype "passive"))
      (node (ref "IC8") (pin "7") (pinfunction "A0_7") (pintype "passive"))
      (node (ref "IC9") (pin "5") (pinfunction "GND_5") (pintype "power_in"))
      (node (ref "J8") (pin "2") (pinfunction "Y_2") (pintype "passive"))
      (node (ref "J9") (pin "2") (pinfunction "Y_2") (pintype "passive"))
      (node (ref "MECH11") (pin "1") (pinfunction "GND_1") (pintype "passive"))
      (node (ref "MECH12") (pin "1") (pinfunction "GND_1") (pintype "passive"))
      (node (ref "MECH13") (pin "1") (pinfunction "GND_1") (pintype "passive"))
      (node (ref "MECH14") (pin "1") (pinfunction "GND_1") (pintype "passive"))
      (node (ref "R63") (pin "1") (pinfunction "1_1") (pintype "passive"))
      (node (ref "R68") (pin "2") (pinfunction "2_2") (pintype "passive"))
      (node (ref "R74") (pin "1") (pinfunction "1_1") (pintype "passive"))
      (node (ref "R81") (pin "2") (pinfunction "2_2") (pintype "passive"))
      (node (ref "R83") (pin "1") (pinfunction "1_1") (pintype "passive"))
      (node (ref "R85") (pin "1") (pinfunction "1_1") (pintype "passive"))
      (node (ref "VT4") (pin "S") (pinfunction "S_S") (pintype "passive"))
      (node (ref "XO1") (pin "4") (pinfunction "GND_4") (pintype "passive"))
    )
    (net (code "26") (name "Net-(C148-Pad1)") (class "Default")
      (node (ref "C148") (pin "1") (pinfunction "1_1") (pintype "passive"))
      (node (ref "C149") (pin "2") (pinfunction "2_2") (pintype "passive"))
      (node (ref "R63") (pin "2") (pinfunction "2_2") (pintype "passive"))
    )
    (net (code "27") (name "Net-(C148-Pad2)") (class "Default")
      (node (ref "C148") (pin "2") (pinfunction "2_2") (pintype "passive"))
      (node (ref "R59") (pin "2") (pinfunction "2_2") (pintype "passive"))
      (node (ref "R62") (pin "2") (pinfunction "2_2") (pintype "passive"))
    )
    (net (code "28") (name "Net-(C153-Pad2)") (class "Default")
      (node (ref "C153") (pin "2") (pinfunction "2_2") (pintype "passive"))
      (node (ref "FR15") (pin "1") (pinfunction "1_1") (pintype "passive"))
      (node (ref "R60") (pin "1") (pinfunction "1_1") (pintype "passive"))
    )
    (net (code "29") (name "Net-(C172-Pad1)") (class "Default")
      (node (ref "C172") (pin "1") (pinfunction "1_1") (pintype "passive"))
      (node (ref "J10") (pin "2") (pinfunction "2_2") (pintype "passive"))
      (node (ref "R69") (pin "2") (pinfunction "2_2") (pintype "passive"))
      (node (ref "R71") (pin "2") (pinfunction "2_2") (pintype "passive"))
    )
    (net (code "30") (name "Net-(IC7-CLKin)") (class "Default")
      (node (ref "C149") (pin "1") (pinfunction "1_1") (pintype "passive"))
      (node (ref "IC7") (pin "21") (pinfunction "CLKin_21") (pintype "passive"))
    )
    (net (code "31") (name "Net-(IC7-CLKin*)") (class "Default")
      (node (ref "C156") (pin "2") (pinfunction "2_2") (pintype "passive"))
      (node (ref "IC7") (pin "20") (pinfunction "CLKin*_20") (pintype "passive"))
    )
    (net (code "32") (name "Net-(IC7-CLKout0)") (class "Default")
      (node (ref "IC7") (pin "3") (pinfunction "CLKout0_3") (pintype "passive"))
      (node (ref "R61") (pin "2") (pinfunction "2_2") (pintype "passive"))
    )
    (net (code "33") (name "Net-(IC7-CLKout1)") (class "Default")
      (node (ref "IC7") (pin "5") (pinfunction "CLKout1_5") (pintype "passive"))
      (node (ref "R65") (pin "2") (pinfunction "2_2") (pintype "passive"))
    )
    (net (code "34") (name "Net-(IC7-OE)") (class "Default")
      (node (ref "IC7") (pin "24") (pinfunction "OE_24") (pintype "passive"))
      (node (ref "R57") (pin "1") (pinfunction "1_1") (pintype "passive"))
    )
    (net (code "35") (name "Net-(IC9-VDD)") (class "Default")
      (node (ref "C163") (pin "1") (pinfunction "1_1") (pintype "passive"))
      (node (ref "FR17") (pin "2") (pinfunction "2_2") (pintype "passive"))
      (node (ref "IC9") (pin "4") (pinfunction "VDD_4") (pintype "power_in"))
    )
    (net (code "36") (name "Net-(IC9-VOUT)") (class "Default")
      (node (ref "IC9") (pin "6") (pinfunction "VOUT_6") (pintype "tri_state"))
      (node (ref "R67") (pin "2") (pinfunction "2_2") (pintype "passive"))
    )
    (net (code "37") (name "Net-(IC12-FB)") (class "Default")
      (node (ref "IC12") (pin "11") (pinfunction "FB_11") (pintype "passive"))
      (node (ref "R83") (pin "2") (pinfunction "2_2") (pintype "passive"))
    )
    (net (code "38") (name "Net-(IC13-EN)") (class "Default")
      (node (ref "IC13") (pin "1") (pinfunction "EN_1") (pintype "passive"))
      (node (ref "R82") (pin "1") (pinfunction "1_1") (pintype "passive"))
      (node (ref "R84") (pin "2") (pinfunction "2_2") (pintype "passive"))
    )
    (net (code "39") (name "Net-(IC13-FB)") (class "Default")
      (node (ref "IC13") (pin "11") (pinfunction "FB_11") (pintype "passive"))
      (node (ref "R85") (pin "2") (pinfunction "2_2") (pintype "passive"))
    )
    (net (code "40") (name "Net-(IC13-PG)") (class "Default")
      (node (ref "IC13") (pin "10") (pinfunction "PG_10") (pintype "passive"))
      (node (ref "R78") (pin "1") (pinfunction "1_1") (pintype "passive"))
    )
    (net (code "41") (name "Net-(IC14-ADJ)") (class "Default")
      (node (ref "IC14") (pin "5") (pinfunction "ADJ_5") (pintype "input"))
      (node (ref "R80") (pin "1") (pinfunction "1_1") (pintype "passive"))
      (node (ref "R81") (pin "1") (pinfunction "1_1") (pintype "passive"))
    )
    (net (code "42") (name "Net-(IC14-PG)") (class "Default")
      (node (ref "C183") (pin "2") (pinfunction "2_2") (pintype "passive"))
      (node (ref "IC14") (pin "3") (pinfunction "PG_3") (pintype "output"))
    )
    (net (code "43") (name "Net-(IC14-Vout)") (class "Default")
      (node (ref "IC14") (pin "4") (pinfunction "Vout_4") (pintype "output"))
      (node (ref "R79") (pin "1") (pinfunction "1_1") (pintype "passive"))
      (node (ref "R80") (pin "2") (pinfunction "2_2") (pintype "passive"))
    )
    (net (code "44") (name "Net-(J10-Pad1)") (class "Default")
      (node (ref "J10") (pin "1") (pinfunction "1_1") (pintype "passive"))
      (node (ref "R74") (pin "2") (pinfunction "2_2") (pintype "passive"))
      (node (ref "VT4") (pin "D") (pinfunction "D_D") (pintype "passive"))
    )
    (net (code "45") (name "Net-(LED1-Pad3)") (class "Default")
      (node (ref "LED1") (pin "3") (pinfunction "3_3") (pintype "power_in"))
      (node (ref "R70") (pin "1") (pinfunction "1_1") (pintype "passive"))
    )
    (net (code "46") (name "Net-(LED1-Pad4)") (class "Default")
      (node (ref "LED1") (pin "4") (pinfunction "4_4") (pintype "power_in"))
      (node (ref "R72") (pin "1") (pinfunction "1_1") (pintype "passive"))
    )
    (net (code "47") (name "Net-(LED2-PadC1)") (class "Default")
      (node (ref "LED2") (pin "C1") (pinfunction "C1_C1") (pintype "power_in"))
      (node (ref "R75") (pin "1") (pinfunction "1_1") (pintype "passive"))
    )
    (net (code "48") (name "Net-(LED2-PadC2)") (class "Default")
      (node (ref "LED2") (pin "C2") (pinfunction "C2_C2") (pintype "power_in"))
      (node (ref "R73") (pin "1") (pinfunction "1_1") (pintype "passive"))
    )
    (net (code "49") (name "Net-(XO1-RF_OUT)") (class "Default")
      (node (ref "R59") (pin "1") (pinfunction "1_1") (pintype "passive"))
      (node (ref "XO1") (pin "6") (pinfunction "RF_OUT_6") (pintype "output"))
    )
    (net (code "50") (name "Net-(XO1-VCC)") (class "Default")
      (node (ref "C155") (pin "2") (pinfunction "2_2") (pintype "passive"))
      (node (ref "FR15") (pin "2") (pinfunction "2_2") (pintype "passive"))
      (node (ref "XO1") (pin "9") (pinfunction "VCC_9") (pintype "power_in"))
    )
    (net (code "51") (name "Net-(XO1-VC_FILTER)") (class "Default")
      (node (ref "C151") (pin "2") (pinfunction "2_2") (pintype "passive"))
      (node (ref "XO1") (pin "7") (pinfunction "VC_FILTER_7") (pintype "input"))
    )
    (net (code "52") (name "VCC1P8") (class "Default")
      (node (ref "C173") (pin "2") (pinfunction "2_2") (pintype "passive"))
      (node (ref "C174") (pin "1") (pinfunction "1_1") (pintype "passive"))
      (node (ref "C181") (pin "2") (pinfunction "2_2") (pintype "passive"))
      (node (ref "FR16") (pin "1") (pinfunction "1_1") (pintype "passive"))
      (node (ref "FR20") (pin "1") (pinfunction "1_1") (pintype "passive"))
      (node (ref "IC11") (pin "8") (pinfunction "VCC_8") (pintype "power_in"))
      (node (ref "IC12") (pin "7") (pinfunction "VOUT_7") (pintype "passive"))
      (node (ref "IC12") (pin "8") (pinfunction "VOUT_8") (pintype "passive"))
      (node (ref "R58") (pin "2") (pinfunction "2_2") (pintype "passive"))
    )
    (net (code "53") (name "VCC1P8_LMS") (class "Default")
      (node (ref "C175") (pin "2") (pinfunction "2_2") (pintype "passive"))
      (node (ref "FR20") (pin "2") (pinfunction "2_2") (pintype "passive"))
    )
    (net (code "54") (name "VCC3P3") (class "Default")
      (node (ref "C150") (pin "1") (pinfunction "1_1") (pintype "passive"))
      (node (ref "C162") (pin "1") (pinfunction "1_1") (pintype "passive"))
      (node (ref "C178") (pin "2") (pinfunction "2_2") (pintype "passive"))
      (node (ref "C182") (pin "2") (pinfunction "2_2") (pintype "passive"))
      (node (ref "FR22") (pin "1") (pinfunction "1_1") (pintype "passive"))
      (node (ref "IC10") (pin "A1") (pinfunction "VCC_A1") (pintype "passive"))
      (node (ref "IC13") (pin "7") (pinfunction "VOUT_7") (pintype "passive"))
      (node (ref "IC13") (pin "8") (pinfunction "VOUT_8") (pintype "passive"))
      (node (ref "IC14") (pin "1") (pinfunction "EN_1") (pintype "input"))
      (node (ref "IC14") (pin "6") (pinfunction "Vin_6") (pintype "input"))
      (node (ref "IC8") (pin "8") (pinfunction "VCC_8") (pintype "passive"))
      (node (ref "LED1") (pin "1") (pinfunction "1_1") (pintype "power_in"))
      (node (ref "LED1") (pin "2") (pinfunction "2_2") (pintype "power_in"))
      (node (ref "LED2") (pin "A") (pinfunction "A_A") (pintype "power_in"))
      (node (ref "R64") (pin "1") (pinfunction "1_1") (pintype "passive"))
      (node (ref "R66") (pin "1") (pinfunction "1_1") (pintype "passive"))
      (node (ref "R71") (pin "1") (pinfunction "1_1") (pintype "passive"))
      (node (ref "R77") (pin "1") (pinfunction "1_1") (pintype "passive"))
    )
    (net (code "55") (name "VCC3P3_CLK") (class "Default")
      (node (ref "C184") (pin "2") (pinfunction "2_2") (pintype "passive"))
      (node (ref "FR17") (pin "1") (pinfunction "1_1") (pintype "passive"))
      (node (ref "FR19") (pin "1") (pinfunction "1_1") (pintype "passive"))
      (node (ref "FR22") (pin "2") (pinfunction "2_2") (pintype "passive"))
      (node (ref "R60") (pin "2") (pinfunction "2_2") (pintype "passive"))
    )
    (net (code "56") (name "VCC5P0_USB") (class "Default")
      (node (ref "C176") (pin "2") (pinfunction "2_2") (pintype "passive"))
      (node (ref "C177") (pin "2") (pinfunction "2_2") (pintype "passive"))
      (node (ref "IC12") (pin "1") (pinfunction "EN_1") (pintype "passive"))
      (node (ref "IC12") (pin "4") (pinfunction "VIN_4") (pintype "passive"))
      (node (ref "IC12") (pin "5") (pinfunction "VIN_5") (pintype "passive"))
      (node (ref "IC13") (pin "4") (pinfunction "VIN_4") (pintype "passive"))
      (node (ref "IC13") (pin "5") (pinfunction "VIN_5") (pintype "passive"))
      (node (ref "R69") (pin "1") (pinfunction "1_1") (pintype "passive"))
      (node (ref "R76") (pin "2") (pinfunction "2_2") (pintype "passive"))
      (node (ref "R78") (pin "2") (pinfunction "2_2") (pintype "passive"))
      (node (ref "R84") (pin "1") (pinfunction "1_1") (pintype "passive"))
    )
    (net (code "57") (name "VDIO_LMS") (class "Default")
      (node (ref "C180") (pin "2") (pinfunction "2_2") (pintype "passive"))
      (node (ref "FR21") (pin "2") (pinfunction "2_2") (pintype "passive"))
    )
    (net (code "58") (name "VDIO_LMS_FPGA") (class "Default")
      (node (ref "C179") (pin "2") (pinfunction "2_2") (pintype "passive"))
      (node (ref "FR18") (pin "1") (pinfunction "1_1") (pintype "passive"))
      (node (ref "FR21") (pin "1") (pinfunction "1_1") (pintype "passive"))
      (node (ref "R77") (pin "2") (pinfunction "2_2") (pintype "passive"))
      (node (ref "R79") (pin "2") (pinfunction "2_2") (pintype "passive"))
    )
    (net (code "59") (name "VDIO_LMS_LMK") (class "Default")
      (node (ref "C164") (pin "2") (pinfunction "2_2") (pintype "passive"))
      (node (ref "C165") (pin "2") (pinfunction "2_2") (pintype "passive"))
      (node (ref "C166") (pin "2") (pinfunction "2_2") (pintype "passive"))
      (node (ref "C167") (pin "2") (pinfunction "2_2") (pintype "passive"))
      (node (ref "FR18") (pin "2") (pinfunction "2_2") (pintype "passive"))
      (node (ref "IC7") (pin "14") (pinfunction "Vddo_14") (pintype "passive"))
      (node (ref "IC7") (pin "18") (pinfunction "Vddo_18") (pintype "passive"))
    )
    (net (code "60") (name "unconnected-(IC7-CLKout3-Pad15)") (class "Default")
      (node (ref "IC7") (pin "15") (pinfunction "CLKout3_15") (pintype "passive+no_connect"))
    )
    (net (code "61") (name "unconnected-(IC7-OSCin-Pad9)") (class "Default")
      (node (ref "IC7") (pin "9") (pinfunction "OSCin_9") (pintype "passive+no_connect"))
    )
    (net (code "62") (name "unconnected-(IC7-OSCout-Pad10)") (class "Default")
      (node (ref "IC7") (pin "10") (pinfunction "OSCout_10") (pintype "passive+no_connect"))
    )
    (net (code "63") (name "unconnected-(IC12-NC-Pad2)") (class "Default")
      (node (ref "IC12") (pin "2") (pinfunction "NC_2") (pintype "passive+no_connect"))
    )
    (net (code "64") (name "unconnected-(IC12-NC-Pad3)") (class "Default")
      (node (ref "IC12") (pin "3") (pinfunction "NC_3") (pintype "passive+no_connect"))
    )
    (net (code "65") (name "unconnected-(IC12-NC-Pad9)") (class "Default")
      (node (ref "IC12") (pin "9") (pinfunction "NC_9") (pintype "passive+no_connect"))
    )
    (net (code "66") (name "unconnected-(IC12-NC-Pad13)") (class "Default")
      (node (ref "IC12") (pin "13") (pinfunction "NC_13") (pintype "passive+no_connect"))
    )
    (net (code "67") (name "unconnected-(IC12-NC-Pad14)") (class "Default")
      (node (ref "IC12") (pin "14") (pinfunction "NC_14") (pintype "passive+no_connect"))
    )
    (net (code "68") (name "unconnected-(IC13-NC-Pad2)") (class "Default")
      (node (ref "IC13") (pin "2") (pinfunction "NC_2") (pintype "passive+no_connect"))
    )
    (net (code "69") (name "unconnected-(IC13-NC-Pad3)") (class "Default")
      (node (ref "IC13") (pin "3") (pinfunction "NC_3") (pintype "passive+no_connect"))
    )
    (net (code "70") (name "unconnected-(IC13-NC-Pad9)") (class "Default")
      (node (ref "IC13") (pin "9") (pinfunction "NC_9") (pintype "passive+no_connect"))
    )
    (net (code "71") (name "unconnected-(IC13-NC-Pad13)") (class "Default")
      (node (ref "IC13") (pin "13") (pinfunction "NC_13") (pintype "passive+no_connect"))
    )
    (net (code "72") (name "unconnected-(IC13-NC-Pad14)") (class "Default")
      (node (ref "IC13") (pin "14") (pinfunction "NC_14") (pintype "passive+no_connect"))
    )
    (net (code "73") (name "unconnected-(XO1-NC-Pad2)") (class "Default")
      (node (ref "XO1") (pin "2") (pinfunction "NC_2") (pintype "passive+no_connect"))
    )
    (net (code "74") (name "unconnected-(XO1-NC-Pad3)") (class "Default")
      (node (ref "XO1") (pin "3") (pinfunction "NC_3") (pintype "passive+no_connect"))
    )
    (net (code "75") (name "unconnected-(XO1-NC-Pad5)") (class "Default")
      (node (ref "XO1") (pin "5") (pinfunction "NC_5") (pintype "passive+no_connect"))
    )
    (net (code "76") (name "unconnected-(XO1-NC-Pad8)") (class "Default")
      (node (ref "XO1") (pin "8") (pinfunction "NC_8") (pintype "passive+no_connect"))
    )
    (net (code "77") (name "unconnected-(XO1-NC-Pad10)") (class "Default")
      (node (ref "XO1") (pin "10") (pinfunction "NC_10") (pintype "passive+no_connect"))
    )
  )
)
